# NixiePSU.net
KiCad netlist of a schematic drawn in EAGLE
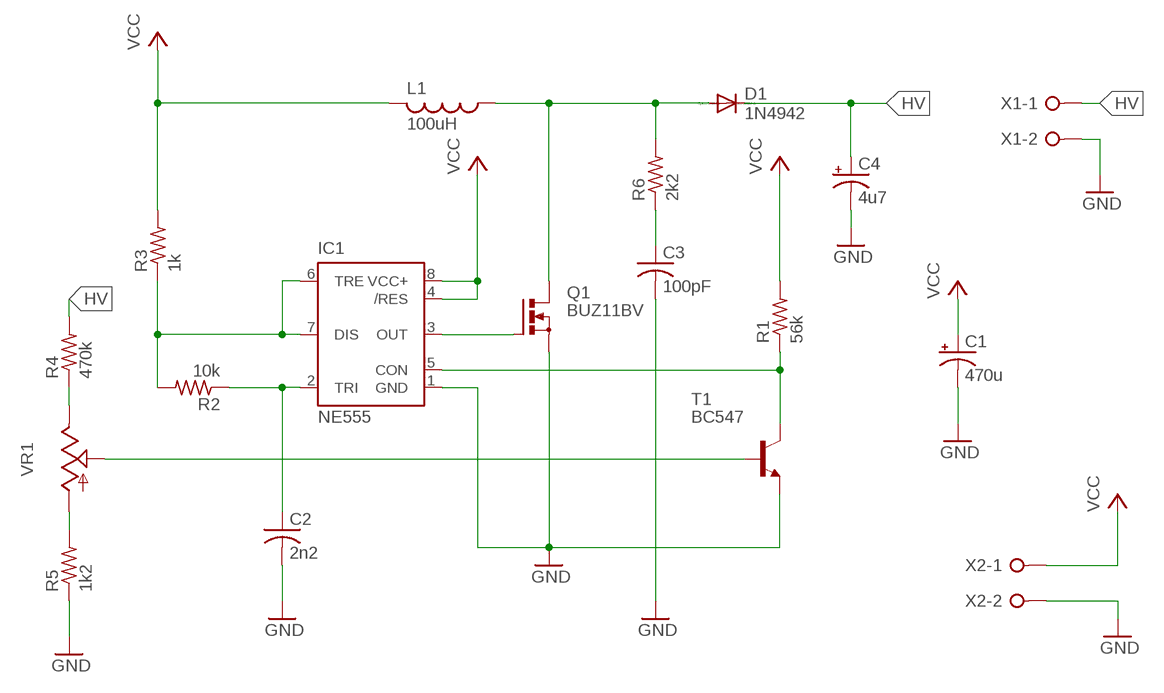
[diagram p0: schematic, sheet 1]

(export (version "E")
  (design (tool "Eeschema 10.0.6"))
  (components
    (comp (ref "C1")
      (value "470u")
      (footprint "eagle-import:E5-13")
      (libsource (lib "eagle-import") (part "CPOL-USE5-13"))
    )
    (comp (ref "C2")
      (value "2n2")
      (footprint "eagle-import:C050-025X075")
      (libsource (lib "eagle-import") (part "C-US050-025X075"))
    )
    (comp (ref "C3")
      (value "100pF")
      (footprint "eagle-import:C050-025X075")
      (libsource (lib "eagle-import") (part "C-US050-025X075"))
    )
    (comp (ref "C4")
      (value "4u7")
      (footprint "eagle-import:E3,5-8")
      (libsource (lib "eagle-import") (part "CPOL-USE3.5-8"))
    )
    (comp (ref "D1")
      (value "1N4942")
      (footprint "eagle-import:DO41-10")
      (libsource (lib "eagle-import") (part "1N4942"))
    )
    (comp (ref "IC1")
      (value "NE555")
      (footprint "eagle-import:DIL-08")
      (fields (field (name "MF") "Arrow Electronics") (field (name "MPN") "NE555N"))
      (libsource (lib "eagle-import") (part "NE555"))
    )
    (comp (ref "L1")
      (value "100uH")
      (footprint "eagle-import:RLB0914")
      (libsource (lib "eagle-import") (part "L-US"))
    )
    (comp (ref "Q1")
      (value "BUZ11BV")
      (footprint "eagle-import:TO220BV")
      (libsource (lib "eagle-import") (part "BUZ11BV"))
    )
    (comp (ref "R1")
      (value "56k")
      (footprint "eagle-import:0207_10")
      (libsource (lib "eagle-import") (part "R-US_0207/10"))
    )
    (comp (ref "R2")
      (value "10k")
      (footprint "eagle-import:0207_10")
      (libsource (lib "eagle-import") (part "R-US_0207/10"))
    )
    (comp (ref "R3")
      (value "1k")
      (footprint "eagle-import:0207_10")
      (libsource (lib "eagle-import") (part "R-US_0207/10"))
    )
    (comp (ref "R4")
      (value "470k")
      (footprint "eagle-import:0207_10")
      (libsource (lib "eagle-import") (part "R-US_0207/10"))
    )
    (comp (ref "R5")
      (value "1k2")
      (footprint "eagle-import:0207_10")
      (libsource (lib "eagle-import") (part "R-US_0207/10"))
    )
    (comp (ref "R6")
      (value "2k2")
      (footprint "eagle-import:0207_10")
      (libsource (lib "eagle-import") (part "R-US_0207/10"))
    )
    (comp (ref "T1")
      (value "BC547")
      (footprint "eagle-import:TO92")
      (libsource (lib "eagle-import") (part "BC547"))
    )
    (comp (ref "VR1")
      (value "TRIM_US-B25P")
      (footprint "eagle-import:B25P")
      (libsource (lib "eagle-import") (part "TRIM_US-B25P"))
    )
    (comp (ref "X1")
      (value "W237-02P")
      (footprint "eagle-import:W237-132")
      (libsource (lib "eagle-import") (part "W237-02P"))
    )
    (comp (ref "X2")
      (value "W237-02P")
      (footprint "eagle-import:W237-132")
      (libsource (lib "eagle-import") (part "W237-02P"))
    )
  )
  (nets
    (net (code "1") (name "GND") (class "Default")
      (node (ref "C1") (pin "-") (pinfunction "-_-") (pintype "passive"))
      (node (ref "C2") (pin "2") (pinfunction "2_2") (pintype "passive"))
      (node (ref "C3") (pin "2") (pinfunction "2_2") (pintype "passive"))
      (node (ref "C4") (pin "-") (pinfunction "-_-") (pintype "passive"))
      (node (ref "IC1") (pin "1") (pinfunction "GND_1") (pintype "power_in"))
      (node (ref "Q1") (pin "S") (pinfunction "S_S") (pintype "passive"))
      (node (ref "R5") (pin "1") (pinfunction "1_1") (pintype "passive"))
      (node (ref "T1") (pin "1") (pinfunction "E_1") (pintype "passive"))
      (node (ref "X1") (pin "2") (pinfunction "KL_2") (pintype "passive"))
      (node (ref "X2") (pin "2") (pinfunction "KL_2") (pintype "passive"))
    )
    (net (code "2") (name "HV") (class "Default")
      (node (ref "C4") (pin "+") (pinfunction "+_+") (pintype "passive"))
      (node (ref "D1") (pin "C") (pinfunction "C_C") (pintype "passive"))
      (node (ref "R4") (pin "2") (pinfunction "2_2") (pintype "passive"))
      (node (ref "X1") (pin "1") (pinfunction "KL_1") (pintype "passive"))
    )
    (net (code "3") (name "Net-(C3-Pad1)") (class "Default")
      (node (ref "C3") (pin "1") (pinfunction "1_1") (pintype "passive"))
      (node (ref "R6") (pin "1") (pinfunction "1_1") (pintype "passive"))
    )
    (net (code "4") (name "Net-(D1-PadA)") (class "Default")
      (node (ref "D1") (pin "A") (pinfunction "A_A") (pintype "passive"))
      (node (ref "L1") (pin "1") (pinfunction "1_1") (pintype "passive"))
      (node (ref "Q1") (pin "D") (pinfunction "D_D") (pintype "passive"))
      (node (ref "R6") (pin "2") (pinfunction "2_2") (pintype "passive"))
    )
    (net (code "5") (name "Net-(IC1-CON)") (class "Default")
      (node (ref "IC1") (pin "5") (pinfunction "CON_5") (pintype "input"))
      (node (ref "R1") (pin "1") (pinfunction "1_1") (pintype "passive"))
      (node (ref "T1") (pin "3") (pinfunction "C_3") (pintype "passive"))
    )
    (net (code "6") (name "Net-(IC1-DIS)") (class "Default")
      (node (ref "IC1") (pin "6") (pinfunction "TRE_6") (pintype "input"))
      (node (ref "IC1") (pin "7") (pinfunction "DIS_7") (pintype "input"))
      (node (ref "R2") (pin "2") (pinfunction "2_2") (pintype "passive"))
      (node (ref "R3") (pin "1") (pinfunction "1_1") (pintype "passive"))
    )
    (net (code "7") (name "Net-(IC1-OUT)") (class "Default")
      (node (ref "IC1") (pin "3") (pinfunction "OUT_3") (pintype "output"))
      (node (ref "Q1") (pin "G") (pinfunction "G_G") (pintype "passive"))
    )
    (net (code "8") (name "Net-(IC1-TRI)") (class "Default")
      (node (ref "C2") (pin "1") (pinfunction "1_1") (pintype "passive"))
      (node (ref "IC1") (pin "2") (pinfunction "TRI_2") (pintype "input"))
      (node (ref "R2") (pin "1") (pinfunction "1_1") (pintype "passive"))
    )
    (net (code "9") (name "Net-(R4-Pad1)") (class "Default")
      (node (ref "R4") (pin "1") (pinfunction "1_1") (pintype "passive"))
      (node (ref "VR1") (pin "E") (pinfunction "E_E") (pintype "passive"))
    )
    (net (code "10") (name "Net-(R5-Pad2)") (class "Default")
      (node (ref "R5") (pin "2") (pinfunction "2_2") (pintype "passive"))
      (node (ref "VR1") (pin "A") (pinfunction "A_A") (pintype "passive"))
    )
    (net (code "11") (name "Net-(T1-B)") (class "Default")
      (node (ref "T1") (pin "2") (pinfunction "B_2") (pintype "passive"))
      (node (ref "VR1") (pin "S") (pinfunction "S_S") (pintype "passive"))
    )
    (net (code "12") (name "VCC") (class "Default")
      (node (ref "C1") (pin "+") (pinfunction "+_+") (pintype "passive"))
      (node (ref "IC1") (pin "4") (pinfunction "/RES_4") (pintype "input"))
      (node (ref "IC1") (pin "8") (pinfunction "VCC+_8") (pintype "power_in"))
      (node (ref "L1") (pin "2") (pinfunction "2_2") (pintype "passive"))
      (node (ref "R1") (pin "2") (pinfunction "2_2") (pintype "passive"))
      (node (ref "R3") (pin "2") (pinfunction "2_2") (pintype "passive"))
      (node (ref "X2") (pin "1") (pinfunction "KL_1") (pintype "passive"))
    )
  )
)
